# System.net
KiCad netlist of a schematic drawn in Altium Designer
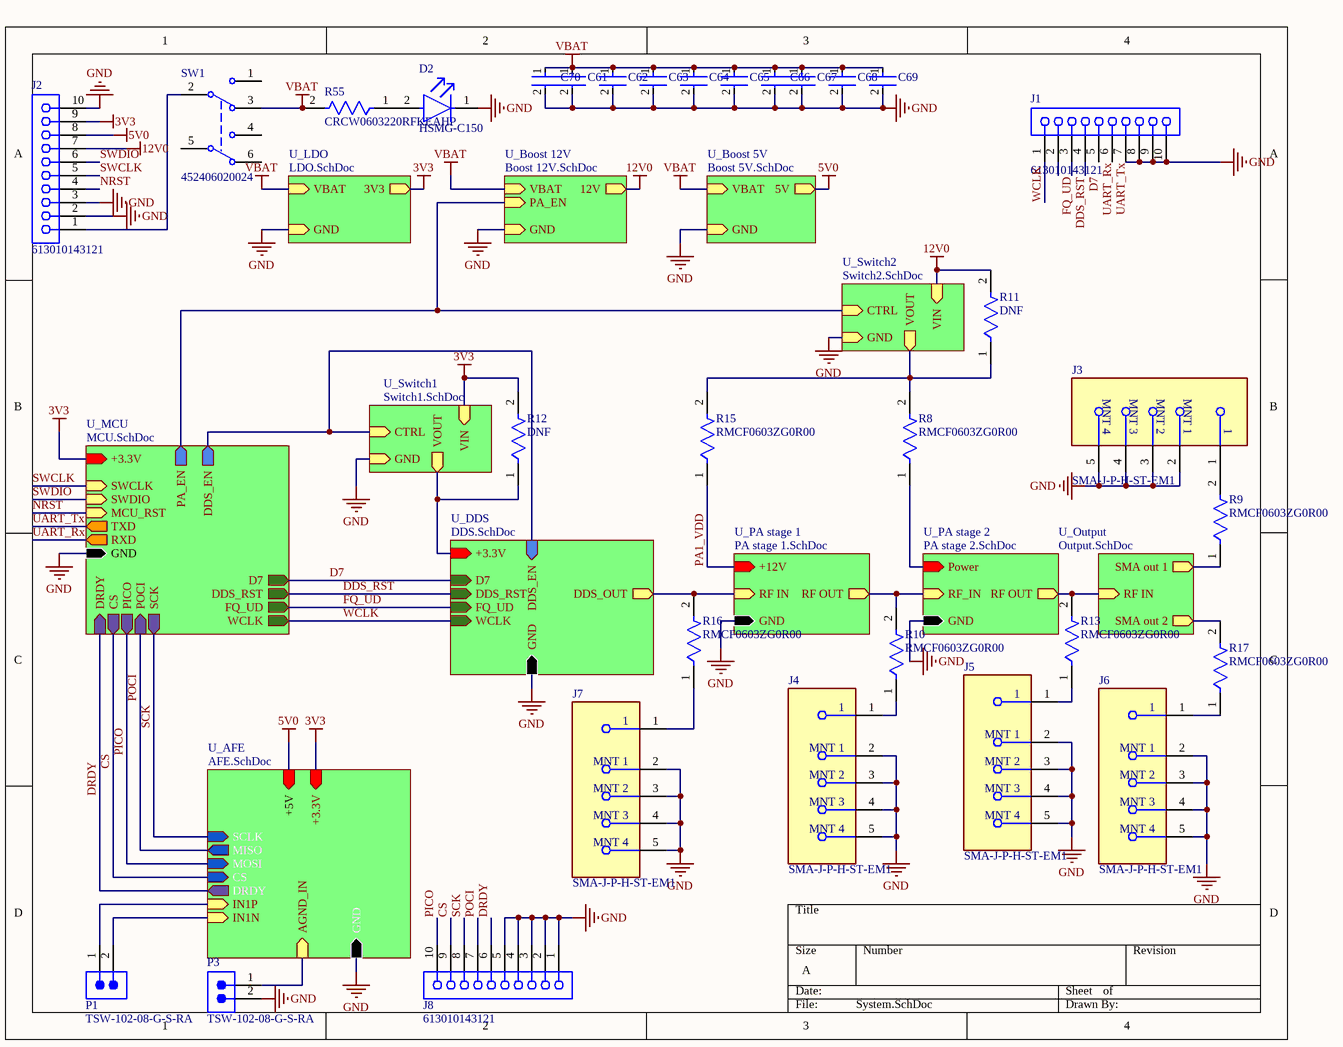
[diagram p0: System.SchDoc]

(export (version "E")
  (design (tool "Eeschema 10.0.6"))
  (components
    (comp (ref "C61")
      (value "GRM21BR60J107ME15K")
      (footprint "FP-GRM21B-0_2-e0_2_0_7-IPC_B")
      (description "Chip Multilayer Ceramic Capacitors for General Purpose, 0805, 100uF, X5R, 15%, 20%, 6.3V")
      (fields (field (name "TOLERANCE") "20%"))
      (libsource (lib "Altium Content Vault") (part "b4654b650e69147ec39a6b967a45e02"))
    )
    (comp (ref "C62")
      (value "GRM21BR60J107ME15K")
      (footprint "FP-GRM21B-0_2-e0_2_0_7-IPC_B")
      (description "Chip Multilayer Ceramic Capacitors for General Purpose, 0805, 100uF, X5R, 15%, 20%, 6.3V")
      (fields (field (name "TOLERANCE") "20%"))
      (libsource (lib "Altium Content Vault") (part "b4654b650e69147ec39a6b967a45e02"))
    )
    (comp (ref "C63")
      (value "GRM21BR60J107ME15K")
      (footprint "FP-GRM21B-0_2-e0_2_0_7-IPC_B")
      (description "Chip Multilayer Ceramic Capacitors for General Purpose, 0805, 100uF, X5R, 15%, 20%, 6.3V")
      (fields (field (name "TOLERANCE") "20%"))
      (libsource (lib "Altium Content Vault") (part "b4654b650e69147ec39a6b967a45e02"))
    )
    (comp (ref "C64")
      (value "GRM21BR60J107ME15K")
      (footprint "FP-GRM21B-0_2-e0_2_0_7-IPC_B")
      (description "Chip Multilayer Ceramic Capacitors for General Purpose, 0805, 100uF, X5R, 15%, 20%, 6.3V")
      (fields (field (name "TOLERANCE") "20%"))
      (libsource (lib "Altium Content Vault") (part "b4654b650e69147ec39a6b967a45e02"))
    )
    (comp (ref "C65")
      (value "GRM21BR60J107ME15K")
      (footprint "FP-GRM21B-0_2-e0_2_0_7-IPC_B")
      (description "Chip Multilayer Ceramic Capacitors for General Purpose, 0805, 100uF, X5R, 15%, 20%, 6.3V")
      (fields (field (name "TOLERANCE") "20%"))
      (libsource (lib "Altium Content Vault") (part "b4654b650e69147ec39a6b967a45e02"))
    )
    (comp (ref "C66")
      (value "GRM21BR60J107ME15K")
      (footprint "FP-GRM21B-0_2-e0_2_0_7-IPC_B")
      (description "Chip Multilayer Ceramic Capacitors for General Purpose, 0805, 100uF, X5R, 15%, 20%, 6.3V")
      (fields (field (name "TOLERANCE") "20%"))
      (libsource (lib "Altium Content Vault") (part "b4654b650e69147ec39a6b967a45e02"))
    )
    (comp (ref "C67")
      (value "GRM21BR60J107ME15K")
      (footprint "FP-GRM21B-0_2-e0_2_0_7-IPC_B")
      (description "Chip Multilayer Ceramic Capacitors for General Purpose, 0805, 100uF, X5R, 15%, 20%, 6.3V")
      (fields (field (name "TOLERANCE") "20%"))
      (libsource (lib "Altium Content Vault") (part "b4654b650e69147ec39a6b967a45e02"))
    )
    (comp (ref "C68")
      (value "GRM21BR60J107ME15K")
      (footprint "FP-GRM21B-0_2-e0_2_0_7-IPC_B")
      (description "Chip Multilayer Ceramic Capacitors for General Purpose, 0805, 100uF, X5R, 15%, 20%, 6.3V")
      (fields (field (name "TOLERANCE") "20%"))
      (libsource (lib "Altium Content Vault") (part "b4654b650e69147ec39a6b967a45e02"))
    )
    (comp (ref "C69")
      (value "GRM21BR60J107ME15K")
      (footprint "FP-GRM21B-0_2-e0_2_0_7-IPC_B")
      (description "Chip Multilayer Ceramic Capacitors for General Purpose, 0805, 100uF, X5R, 15%, 20%, 6.3V")
      (fields (field (name "TOLERANCE") "20%"))
      (libsource (lib "Altium Content Vault") (part "b4654b650e69147ec39a6b967a45e02"))
    )
    (comp (ref "C70")
      (value "GRM21BR60J107ME15K")
      (footprint "FP-GRM21B-0_2-e0_2_0_7-IPC_B")
      (description "Chip Multilayer Ceramic Capacitors for General Purpose, 0805, 100uF, X5R, 15%, 20%, 6.3V")
      (fields (field (name "TOLERANCE") "20%"))
      (libsource (lib "Altium Content Vault") (part "b4654b650e69147ec39a6b967a45e02"))
    )
    (comp (ref "D2")
      (value "HSMG-C150")
      (footprint "FP-HSMG-C150-MFG")
      (description "LED GREEN DIFFUSED 1206 SMD")
      (fields
        (field (name "MANUFACTURER") "Broadcom")
        (field (name "OCTOPART") "https://octopart.com/hsmg-c150-broadcom-71131304")
      )
      (libsource (lib "Altium Content Vault") (part "8706943c75ba83719d021d2fdc84c58"))
    )
    (comp (ref "J1")
      (value "613010143121")
      (footprint "613010143121")
      (libsource (lib "Altium Content Vault") (part "Header_Female_1R_10P"))
    )
    (comp (ref "J2")
      (value "613010143121")
      (footprint "613010143121")
      (libsource (lib "Altium Content Vault") (part "Header_Female_1R_10P"))
    )
    (comp (ref "J3")
      (value "SMA-J-P-H-ST-EM1")
      (footprint "FP-SMA-J-P-H-ST-EM1-MFG")
      (description "CONN SMA JACK STR 50OHM EDGE MNT")
      (libsource (lib "") (part "c65b8a639cdaef1819ea20b5466f8fa_1"))
    )
    (comp (ref "J4")
      (value "SMA-J-P-H-ST-EM1")
      (footprint "FP-SMA-J-P-H-ST-EM1-MFG")
      (description "CONN SMA JACK STR 50OHM EDGE MNT")
      (libsource (lib "Altium Content Vault") (part "c65b8a639cdaef1819ea20b5466f8fa"))
    )
    (comp (ref "J5")
      (value "SMA-J-P-H-ST-EM1")
      (footprint "FP-SMA-J-P-H-ST-EM1-MFG")
      (description "CONN SMA JACK STR 50OHM EDGE MNT")
      (libsource (lib "Altium Content Vault") (part "c65b8a639cdaef1819ea20b5466f8fa"))
    )
    (comp (ref "J6")
      (value "SMA-J-P-H-ST-EM1")
      (footprint "FP-SMA-J-P-H-ST-EM1-MFG")
      (description "CONN SMA JACK STR 50OHM EDGE MNT")
      (libsource (lib "Altium Content Vault") (part "c65b8a639cdaef1819ea20b5466f8fa"))
    )
    (comp (ref "J7")
      (value "SMA-J-P-H-ST-EM1")
      (footprint "FP-SMA-J-P-H-ST-EM1-MFG")
      (description "CONN SMA JACK STR 50OHM EDGE MNT")
      (libsource (lib "Altium Content Vault") (part "c65b8a639cdaef1819ea20b5466f8fa"))
    )
    (comp (ref "J8")
      (value "613010143121")
      (footprint "613010143121")
      (libsource (lib "Altium Content Vault") (part "Header_Female_1R_10P"))
    )
    (comp (ref "P1")
      (value "TSW-102-08-G-S-RA")
      (footprint "SMTC-TSW-102-08-X-S-RA")
      (fields (field (name "MANUFACTURER") "Samtec"))
      (libsource (lib "Altium Content Vault") (part "SMTC-TSW-102-X-X-S-X"))
    )
    (comp (ref "P3")
      (value "TSW-102-08-G-S-RA")
      (footprint "SMTC-TSW-102-08-X-S-RA")
      (fields (field (name "MANUFACTURER") "Samtec"))
      (libsource (lib "Altium Content Vault") (part "SMTC-TSW-102-X-X-S-X"))
    )
    (comp (ref "R8")
      (value "RMCF0603ZG0R00")
      (footprint "FP-RMCF0603-IPC_B")
      (description "0Ω ±0 0.1W 0603 Thick Film Chip Resistor AEC-Q200 compliant")
      (libsource (lib "Altium Content Vault") (part "1029c3af85768c4190bb7ad29bc67b5"))
    )
    (comp (ref "R9")
      (value "RMCF0603ZG0R00")
      (footprint "FP-RMCF0603-IPC_B")
      (description "0Ω ±0 0.1W 0603 Thick Film Chip Resistor AEC-Q200 compliant")
      (libsource (lib "Altium Content Vault") (part "1029c3af85768c4190bb7ad29bc67b5"))
    )
    (comp (ref "R10")
      (value "RMCF0603ZG0R00")
      (footprint "FP-RMCF0603-IPC_B")
      (description "0Ω ±0 0.1W 0603 Thick Film Chip Resistor AEC-Q200 compliant")
      (libsource (lib "Altium Content Vault") (part "1029c3af85768c4190bb7ad29bc67b5"))
    )
    (comp (ref "R11")
      (value "DNF")
      (footprint "FP-RMCF0603-IPC_B")
      (description "0Ω ±0 0.1W 0603 Thick Film Chip Resistor AEC-Q200 compliant")
      (libsource (lib "Altium Content Vault") (part "1029c3af85768c4190bb7ad29bc67b5"))
    )
    (comp (ref "R12")
      (value "DNF")
      (footprint "FP-RMCF0603-IPC_B")
      (description "0Ω ±0 0.1W 0603 Thick Film Chip Resistor AEC-Q200 compliant")
      (libsource (lib "Altium Content Vault") (part "1029c3af85768c4190bb7ad29bc67b5"))
    )
    (comp (ref "R13")
      (value "RMCF0603ZG0R00")
      (footprint "FP-RMCF0603-IPC_B")
      (description "0Ω ±0 0.1W 0603 Thick Film Chip Resistor AEC-Q200 compliant")
      (libsource (lib "Altium Content Vault") (part "1029c3af85768c4190bb7ad29bc67b5"))
    )
    (comp (ref "R15")
      (value "RMCF0603ZG0R00")
      (footprint "FP-RMCF0603-IPC_B")
      (description "0Ω ±0 0.1W 0603 Thick Film Chip Resistor AEC-Q200 compliant")
      (libsource (lib "Altium Content Vault") (part "1029c3af85768c4190bb7ad29bc67b5"))
    )
    (comp (ref "R16")
      (value "RMCF0603ZG0R00")
      (footprint "FP-RMCF0603-IPC_B")
      (description "0Ω ±0 0.1W 0603 Thick Film Chip Resistor AEC-Q200 compliant")
      (libsource (lib "Altium Content Vault") (part "1029c3af85768c4190bb7ad29bc67b5"))
    )
    (comp (ref "R17")
      (value "RMCF0603ZG0R00")
      (footprint "FP-RMCF0603-IPC_B")
      (description "0Ω ±0 0.1W 0603 Thick Film Chip Resistor AEC-Q200 compliant")
      (libsource (lib "Altium Content Vault") (part "1029c3af85768c4190bb7ad29bc67b5"))
    )
    (comp (ref "R55")
      (value "CRCW0603220RFKEAHP")
      (footprint "FP-CRCW0603-HPe3-IPC_A")
      (description "RES Thick Film, 220Ω, 1%, 0.33W, 100ppm/°C, 0603")
      (fields (field (name "TOLERANCE") "1%"))
      (libsource (lib "Altium Content Vault") (part "1029c3af85768c4190bb7ad29bc67b5"))
    )
    (comp (ref "SW1")
      (value "452406020024")
      (footprint "452406020024")
      (description "Ws-slsv_smt Mini Slide Switch Sa")
      (libsource (lib "Altium Content Vault") (part "DPDT_WS-SLSV"))
    )
  )
  (nets
    (net (code "1") (name "/AGND_IN") (class "Default")
      (node (ref "P3") (pin "1") (pinfunction "1_1") (pintype "passive"))
    )
    (net (code "2") (name "/CS") (class "Default")
      (node (ref "J8") (pin "9") (pinfunction "9_9") (pintype "passive"))
    )
    (net (code "3") (name "/D7") (class "Default")
      (node (ref "J1") (pin "4") (pinfunction "4_4") (pintype "passive"))
    )
    (net (code "5") (name "/DDS_OUT") (class "Default")
      (node (ref "R16") (pin "2") (pinfunction "2_2") (pintype "passive"))
    )
    (net (code "6") (name "/DDS_RST") (class "Default")
      (node (ref "J1") (pin "3") (pinfunction "3_3") (pintype "passive"))
    )
    (net (code "7") (name "/DRDY") (class "Default")
      (node (ref "J8") (pin "6") (pinfunction "6_6") (pintype "passive"))
    )
    (net (code "8") (name "/FQ_UD") (class "Default")
      (node (ref "J1") (pin "2") (pinfunction "2_2") (pintype "passive"))
    )
    (net (code "9") (name "/IN1N") (class "Default")
      (node (ref "P1") (pin "2") (pinfunction "2_2") (pintype "passive"))
    )
    (net (code "10") (name "/IN1P") (class "Default")
      (node (ref "P1") (pin "1") (pinfunction "1_1") (pintype "passive"))
    )
    (net (code "11") (name "/NRST") (class "Default")
      (node (ref "J2") (pin "4") (pinfunction "4_4") (pintype "passive"))
    )
    (net (code "12") (name "/PA1_VDD") (class "Default")
      (node (ref "R15") (pin "1") (pinfunction "1_1") (pintype "passive"))
    )
    (net (code "14") (name "/PICO") (class "Default")
      (node (ref "J8") (pin "10") (pinfunction "10_10") (pintype "passive"))
    )
    (net (code "15") (name "/POCI") (class "Default")
      (node (ref "J8") (pin "7") (pinfunction "7_7") (pintype "passive"))
    )
    (net (code "16") (name "/Power") (class "Default")
      (node (ref "R8") (pin "1") (pinfunction "1_1") (pintype "passive"))
    )
    (net (code "17") (name "/RF OUT") (class "Default")
      (node (ref "R13") (pin "2") (pinfunction "2_2") (pintype "passive"))
    )
    (net (code "18") (name "/RF OUT_1") (class "Default")
      (node (ref "R10") (pin "2") (pinfunction "2_2") (pintype "passive"))
    )
    (net (code "19") (name "/SCK") (class "Default")
      (node (ref "J8") (pin "8") (pinfunction "8_8") (pintype "passive"))
    )
    (net (code "20") (name "/SMA out 1") (class "Default")
      (node (ref "R9") (pin "1") (pinfunction "1_1") (pintype "passive"))
    )
    (net (code "21") (name "/SMA out 2") (class "Default")
      (node (ref "R17") (pin "2") (pinfunction "2_2") (pintype "passive"))
    )
    (net (code "22") (name "/SWCLK") (class "Default")
      (node (ref "J2") (pin "5") (pinfunction "5_5") (pintype "passive"))
    )
    (net (code "23") (name "/SWDIO") (class "Default")
      (node (ref "J2") (pin "6") (pinfunction "6_6") (pintype "passive"))
    )
    (net (code "24") (name "/UART_Rx") (class "Default")
      (node (ref "J1") (pin "5") (pinfunction "5_5") (pintype "passive"))
    )
    (net (code "25") (name "/UART_Tx") (class "Default")
      (node (ref "J1") (pin "6") (pinfunction "6_6") (pintype "passive"))
    )
    (net (code "26") (name "/VOUT") (class "Default")
      (node (ref "R12") (pin "1") (pinfunction "1_1") (pintype "passive"))
    )
    (net (code "27") (name "/VOUT_1") (class "Default")
      (node (ref "R11") (pin "1") (pinfunction "1_1") (pintype "passive"))
      (node (ref "R15") (pin "2") (pinfunction "2_2") (pintype "passive"))
      (node (ref "R8") (pin "2") (pinfunction "2_2") (pintype "passive"))
    )
    (net (code "28") (name "/WCLK") (class "Default")
      (node (ref "J1") (pin "1") (pinfunction "1_1") (pintype "passive"))
    )
    (net (code "29") (name "3V3") (class "Default")
      (node (ref "J2") (pin "9") (pinfunction "9_9") (pintype "passive"))
      (node (ref "R12") (pin "2") (pinfunction "2_2") (pintype "passive"))
    )
    (net (code "30") (name "5V0") (class "Default")
      (node (ref "J2") (pin "8") (pinfunction "8_8") (pintype "passive"))
    )
    (net (code "31") (name "12V0") (class "Default")
      (node (ref "J2") (pin "7") (pinfunction "7_7") (pintype "passive"))
      (node (ref "R11") (pin "2") (pinfunction "2_2") (pintype "passive"))
    )
    (net (code "32") (name "GND") (class "Default")
      (node (ref "C61") (pin "2") (pinfunction "2_2") (pintype "passive"))
      (node (ref "C62") (pin "2") (pinfunction "2_2") (pintype "passive"))
      (node (ref "C63") (pin "2") (pinfunction "2_2") (pintype "passive"))
      (node (ref "C64") (pin "2") (pinfunction "2_2") (pintype "passive"))
      (node (ref "C65") (pin "2") (pinfunction "2_2") (pintype "passive"))
      (node (ref "C66") (pin "2") (pinfunction "2_2") (pintype "passive"))
      (node (ref "C67") (pin "2") (pinfunction "2_2") (pintype "passive"))
      (node (ref "C68") (pin "2") (pinfunction "2_2") (pintype "passive"))
      (node (ref "C69") (pin "2") (pinfunction "2_2") (pintype "passive"))
      (node (ref "C70") (pin "2") (pinfunction "2_2") (pintype "passive"))
      (node (ref "D2") (pin "1") (pinfunction "C_1") (pintype "passive"))
      (node (ref "J1") (pin "10") (pinfunction "10_10") (pintype "passive"))
      (node (ref "J1") (pin "7") (pinfunction "7_7") (pintype "passive"))
      (node (ref "J1") (pin "8") (pinfunction "8_8") (pintype "passive"))
      (node (ref "J1") (pin "9") (pinfunction "9_9") (pintype "passive"))
      (node (ref "J2") (pin "10") (pinfunction "10_10") (pintype "passive"))
      (node (ref "J2") (pin "2") (pinfunction "2_2") (pintype "passive"))
      (node (ref "J2") (pin "3") (pinfunction "3_3") (pintype "passive"))
      (node (ref "J3") (pin "2") (pinfunction "MNT_1_2") (pintype "passive"))
      (node (ref "J3") (pin "3") (pinfunction "MNT_2_3") (pintype "passive"))
      (node (ref "J3") (pin "4") (pinfunction "MNT_3_4") (pintype "passive"))
      (node (ref "J3") (pin "5") (pinfunction "MNT_4_5") (pintype "passive"))
      (node (ref "J4") (pin "2") (pinfunction "MNT_1_2") (pintype "passive"))
      (node (ref "J4") (pin "3") (pinfunction "MNT_2_3") (pintype "passive"))
      (node (ref "J4") (pin "4") (pinfunction "MNT_3_4") (pintype "passive"))
      (node (ref "J4") (pin "5") (pinfunction "MNT_4_5") (pintype "passive"))
      (node (ref "J5") (pin "2") (pinfunction "MNT_1_2") (pintype "passive"))
      (node (ref "J5") (pin "3") (pinfunction "MNT_2_3") (pintype "passive"))
      (node (ref "J5") (pin "4") (pinfunction "MNT_3_4") (pintype "passive"))
      (node (ref "J5") (pin "5") (pinfunction "MNT_4_5") (pintype "passive"))
      (node (ref "J6") (pin "2") (pinfunction "MNT_1_2") (pintype "passive"))
      (node (ref "J6") (pin "3") (pinfunction "MNT_2_3") (pintype "passive"))
      (node (ref "J6") (pin "4") (pinfunction "MNT_3_4") (pintype "passive"))
      (node (ref "J6") (pin "5") (pinfunction "MNT_4_5") (pintype "passive"))
      (node (ref "J7") (pin "2") (pinfunction "MNT_1_2") (pintype "passive"))
      (node (ref "J7") (pin "3") (pinfunction "MNT_2_3") (pintype "passive"))
      (node (ref "J7") (pin "4") (pinfunction "MNT_3_4") (pintype "passive"))
      (node (ref "J7") (pin "5") (pinfunction "MNT_4_5") (pintype "passive"))
      (node (ref "J8") (pin "1") (pinfunction "1_1") (pintype "passive"))
      (node (ref "J8") (pin "2") (pinfunction "2_2") (pintype "passive"))
      (node (ref "J8") (pin "3") (pinfunction "3_3") (pintype "passive"))
      (node (ref "J8") (pin "4") (pinfunction "4_4") (pintype "passive"))
      (node (ref "J8") (pin "5") (pinfunction "5_5") (pintype "passive"))
      (node (ref "P3") (pin "2") (pinfunction "2_2") (pintype "passive"))
    )
    (net (code "33") (name "Net-(D2-A)") (class "Default")
      (node (ref "D2") (pin "2") (pinfunction "A_2") (pintype "passive"))
      (node (ref "R55") (pin "1") (pinfunction "1_1") (pintype "passive"))
    )
    (net (code "34") (name "Net-(J2-Pad1)") (class "Default")
      (node (ref "J2") (pin "1") (pinfunction "1_1") (pintype "passive"))
      (node (ref "SW1") (pin "2") (pinfunction "COM_2") (pintype "passive"))
    )
    (net (code "35") (name "Net-(J3-Pad1)") (class "Default")
      (node (ref "J3") (pin "1") (pinfunction "1_1") (pintype "passive"))
      (node (ref "R9") (pin "2") (pinfunction "2_2") (pintype "passive"))
    )
    (net (code "36") (name "Net-(J4-Pad1)") (class "Default")
      (node (ref "J4") (pin "1") (pinfunction "1_1") (pintype "passive"))
      (node (ref "R10") (pin "1") (pinfunction "1_1") (pintype "passive"))
    )
    (net (code "37") (name "Net-(J5-Pad1)") (class "Default")
      (node (ref "J5") (pin "1") (pinfunction "1_1") (pintype "passive"))
      (node (ref "R13") (pin "1") (pinfunction "1_1") (pintype "passive"))
    )
    (net (code "38") (name "Net-(J6-Pad1)") (class "Default")
      (node (ref "J6") (pin "1") (pinfunction "1_1") (pintype "passive"))
      (node (ref "R17") (pin "1") (pinfunction "1_1") (pintype "passive"))
    )
    (net (code "39") (name "Net-(J7-Pad1)") (class "Default")
      (node (ref "J7") (pin "1") (pinfunction "1_1") (pintype "passive"))
      (node (ref "R16") (pin "1") (pinfunction "1_1") (pintype "passive"))
    )
    (net (code "40") (name "VBAT") (class "Default")
      (node (ref "C61") (pin "1") (pinfunction "1_1") (pintype "passive"))
      (node (ref "C62") (pin "1") (pinfunction "1_1") (pintype "passive"))
      (node (ref "C63") (pin "1") (pinfunction "1_1") (pintype "passive"))
      (node (ref "C64") (pin "1") (pinfunction "1_1") (pintype "passive"))
      (node (ref "C65") (pin "1") (pinfunction "1_1") (pintype "passive"))
      (node (ref "C66") (pin "1") (pinfunction "1_1") (pintype "passive"))
      (node (ref "C67") (pin "1") (pinfunction "1_1") (pintype "passive"))
      (node (ref "C68") (pin "1") (pinfunction "1_1") (pintype "passive"))
      (node (ref "C69") (pin "1") (pinfunction "1_1") (pintype "passive"))
      (node (ref "C70") (pin "1") (pinfunction "1_1") (pintype "passive"))
      (node (ref "R55") (pin "2") (pinfunction "2_2") (pintype "passive"))
      (node (ref "SW1") (pin "3") (pinfunction "3_3") (pintype "passive"))
    )
    (net (code "41") (name "unconnected-(SW1-COM-Pad5)") (class "Default")
      (node (ref "SW1") (pin "5") (pinfunction "COM_5") (pintype "passive"))
    )
    (net (code "42") (name "unconnected-(SW1-Pad1)") (class "Default")
      (node (ref "SW1") (pin "1") (pinfunction "1_1") (pintype "passive"))
    )
    (net (code "43") (name "unconnected-(SW1-Pad4)") (class "Default")
      (node (ref "SW1") (pin "4") (pinfunction "4_4") (pintype "passive"))
    )
    (net (code "44") (name "unconnected-(SW1-Pad6)") (class "Default")
      (node (ref "SW1") (pin "6") (pinfunction "6_6") (pintype "passive"))
    )
  )
)
